# Keypad.net
KiCad netlist of a schematic drawn in EAGLE
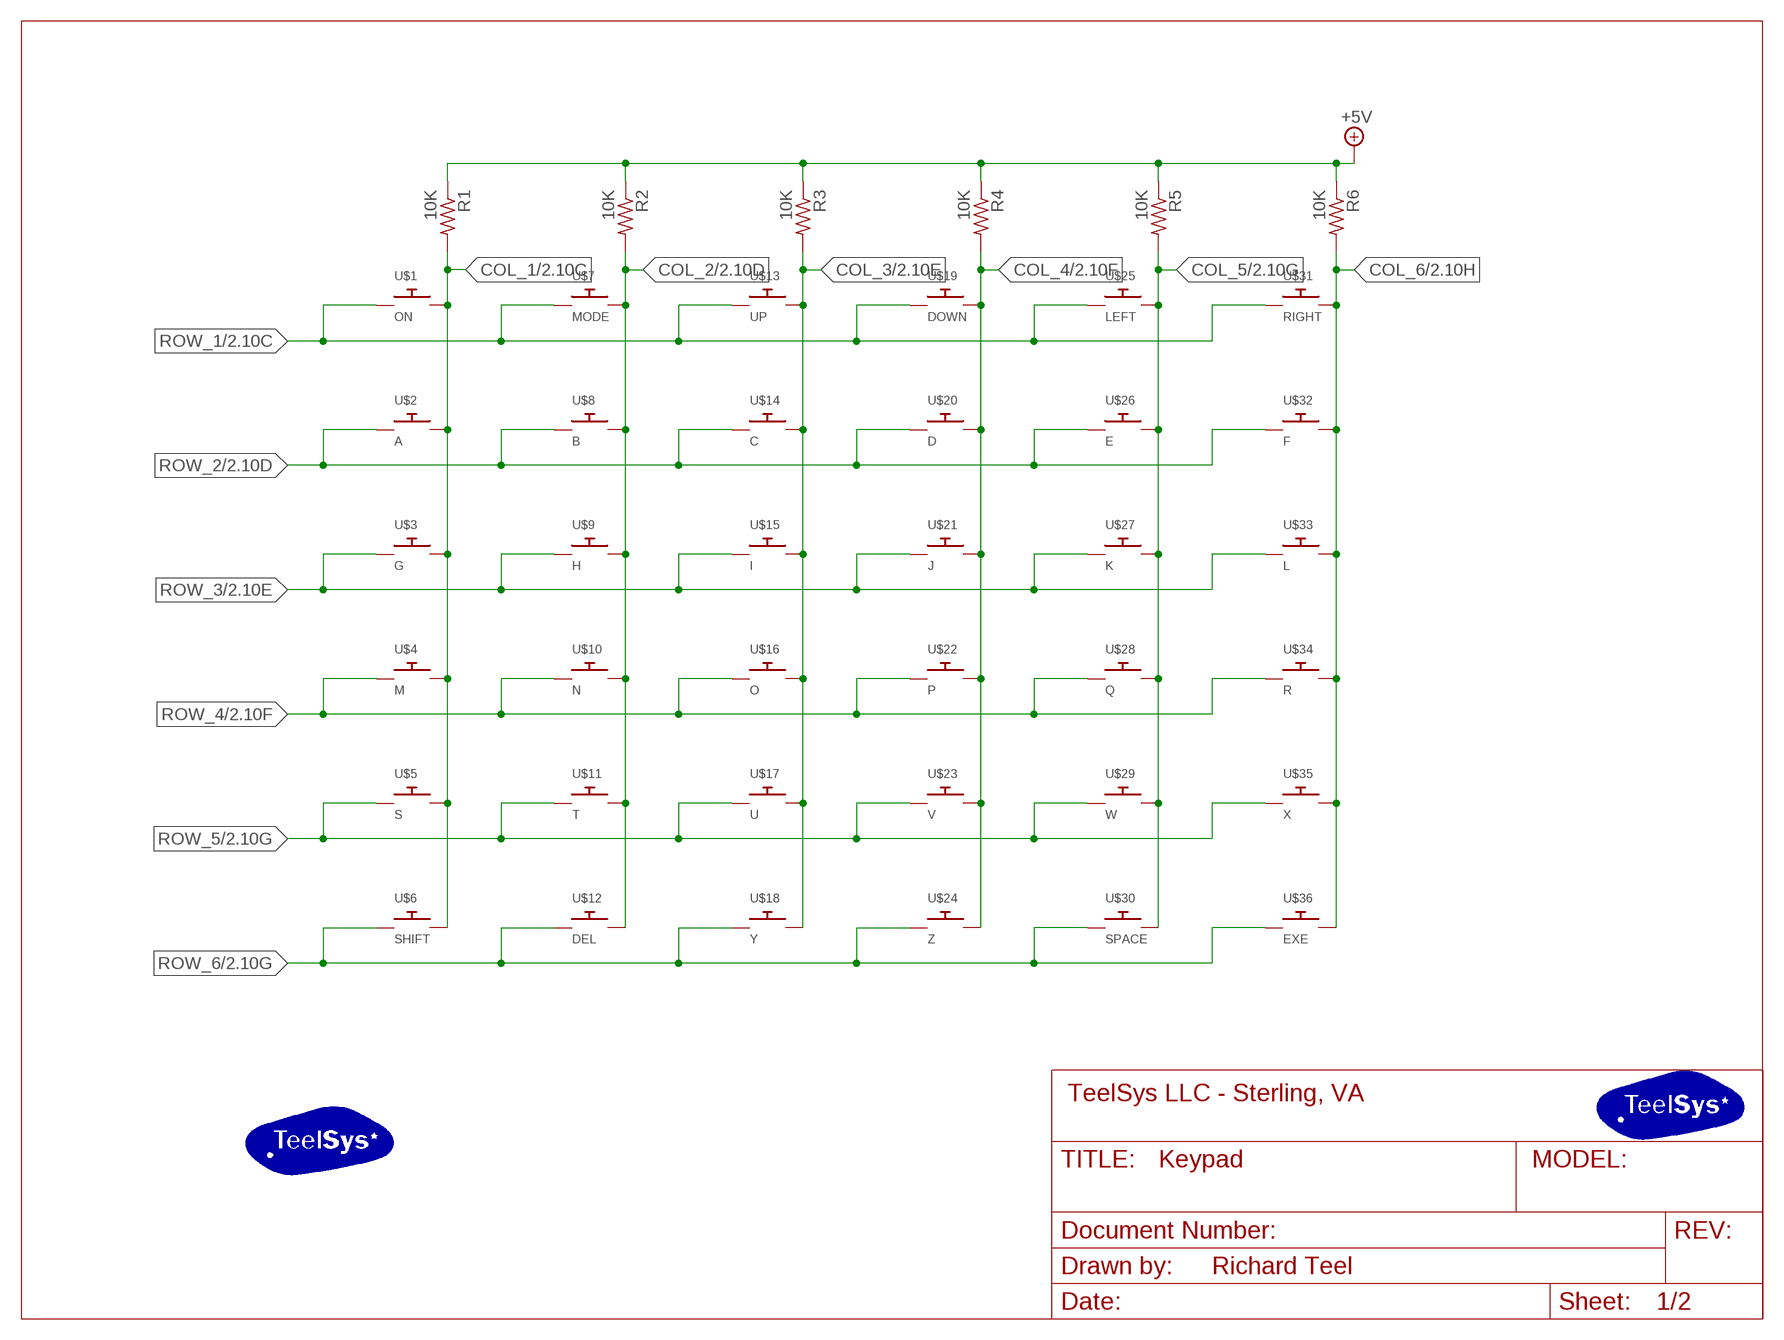
[diagram p0: schematic, sheet 1]
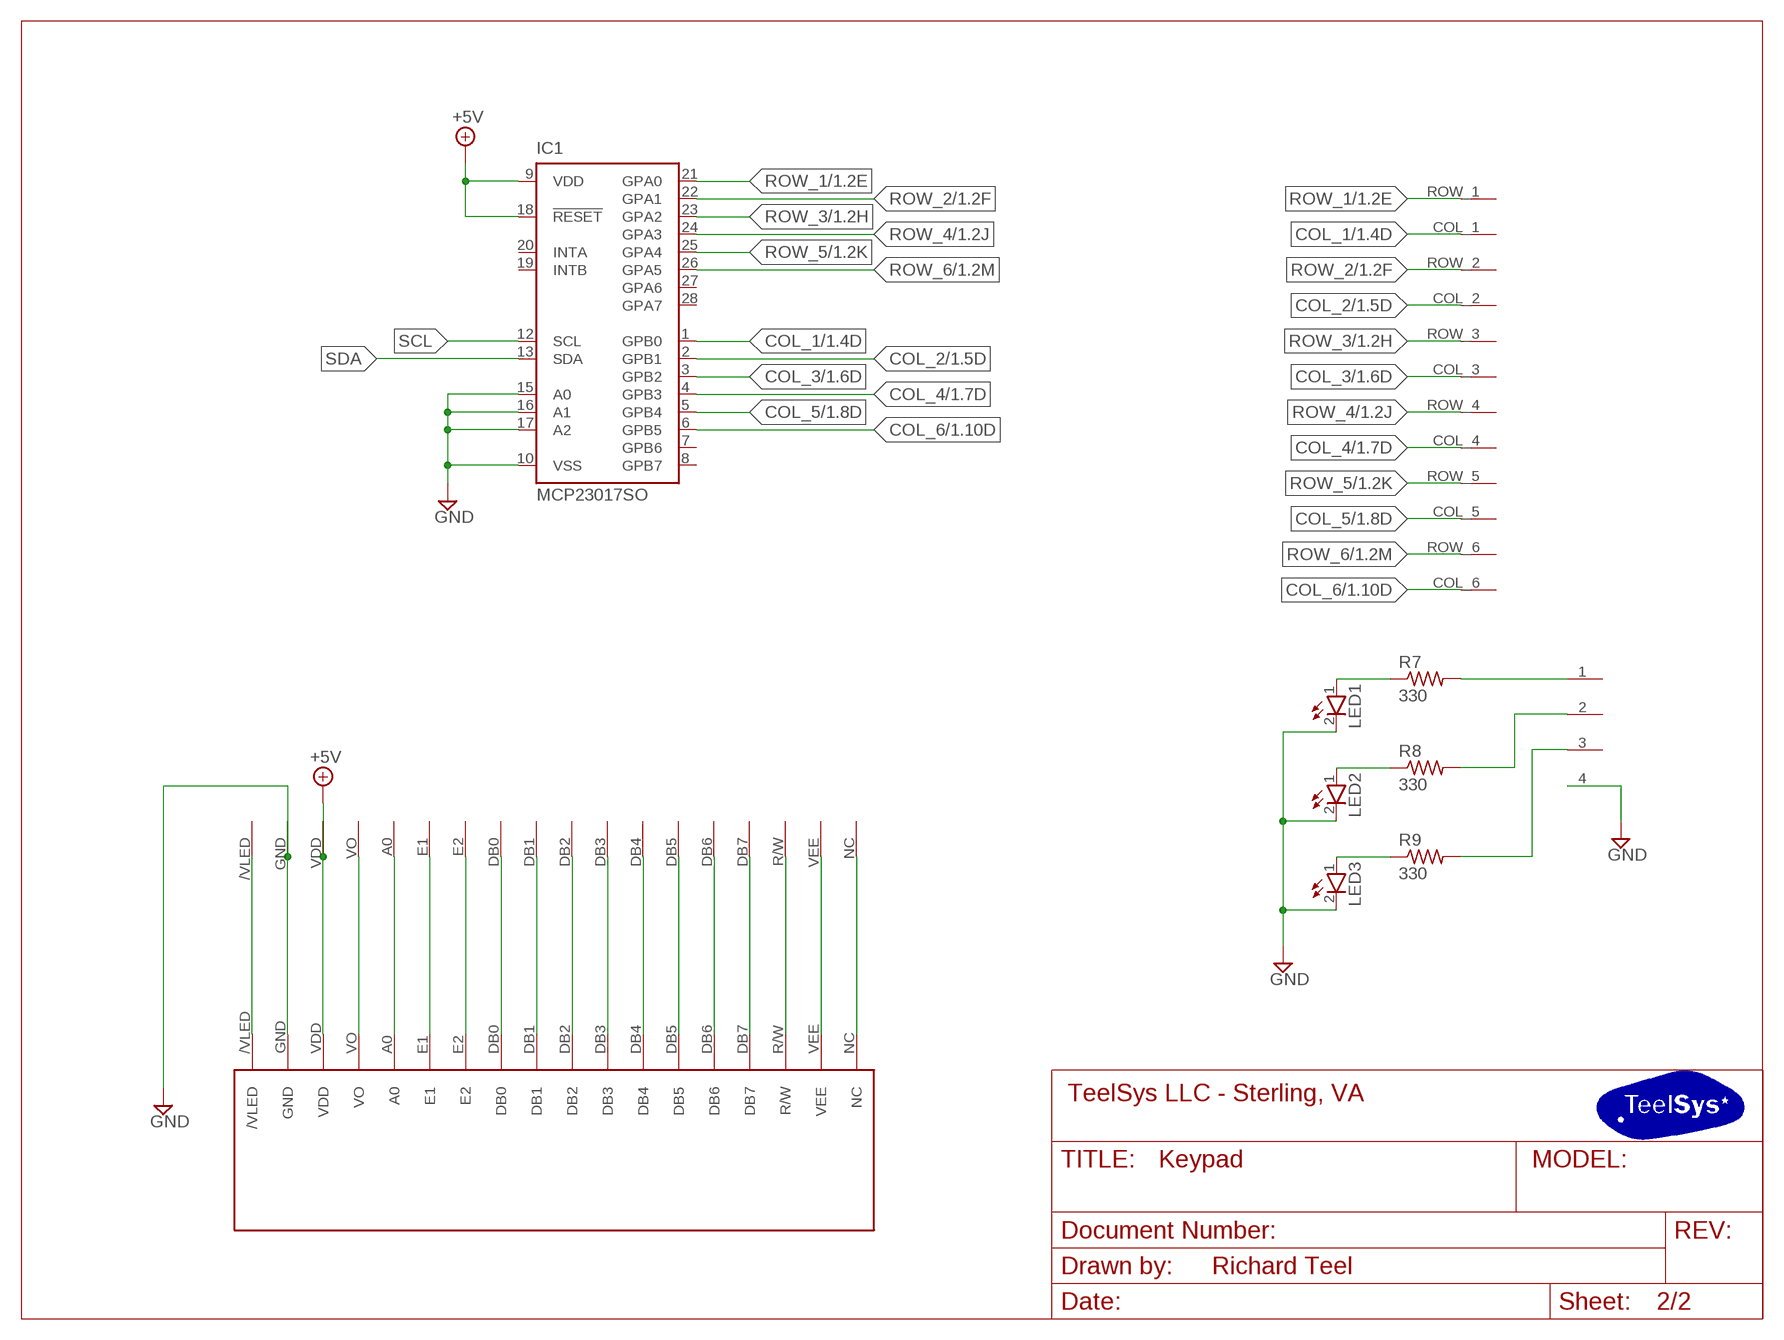
[diagram p1: schematic, sheet 2]

(export (version "E")
  (design (tool "Eeschema 10.0.6"))
  (components
    (comp (ref "R1")
      (value "10K")
      (footprint "eagle-import:M0805")
      (libsource (lib "eagle-import") (part "R-US_M0805"))
    )
    (comp (ref "R2")
      (value "10K")
      (footprint "eagle-import:M0805")
      (libsource (lib "eagle-import") (part "R-US_M0805"))
    )
    (comp (ref "R3")
      (value "10K")
      (footprint "eagle-import:M0805")
      (libsource (lib "eagle-import") (part "R-US_M0805"))
    )
    (comp (ref "R4")
      (value "10K")
      (footprint "eagle-import:M0805")
      (libsource (lib "eagle-import") (part "R-US_M0805"))
    )
    (comp (ref "R5")
      (value "10K")
      (footprint "eagle-import:M0805")
      (libsource (lib "eagle-import") (part "R-US_M0805"))
    )
    (comp (ref "R6")
      (value "10K")
      (footprint "eagle-import:M0805")
      (libsource (lib "eagle-import") (part "R-US_M0805"))
    )
    (comp (ref "U$1")
      (value "ON")
      (footprint "eagle-import:KEYPAD_RND")
      (libsource (lib "eagle-import") (part "KEYPAD"))
    )
    (comp (ref "U$2")
      (value "A")
      (footprint "eagle-import:KEYPAD_RND")
      (libsource (lib "eagle-import") (part "KEYPAD"))
    )
    (comp (ref "U$3")
      (value "G")
      (footprint "eagle-import:KEYPAD_RND")
      (libsource (lib "eagle-import") (part "KEYPAD"))
    )
    (comp (ref "U$4")
      (value "M")
      (footprint "eagle-import:KEYPAD_RND")
      (libsource (lib "eagle-import") (part "KEYPAD"))
    )
    (comp (ref "U$5")
      (value "S")
      (footprint "eagle-import:KEYPAD_RND")
      (libsource (lib "eagle-import") (part "KEYPAD"))
    )
    (comp (ref "U$6")
      (value "SHIFT")
      (footprint "eagle-import:KEYPAD_RND")
      (libsource (lib "eagle-import") (part "KEYPAD"))
    )
    (comp (ref "U$7")
      (value "MODE")
      (footprint "eagle-import:KEYPAD_RND")
      (libsource (lib "eagle-import") (part "KEYPAD"))
    )
    (comp (ref "U$8")
      (value "B")
      (footprint "eagle-import:KEYPAD_RND")
      (libsource (lib "eagle-import") (part "KEYPAD"))
    )
    (comp (ref "U$9")
      (value "H")
      (footprint "eagle-import:KEYPAD_RND")
      (libsource (lib "eagle-import") (part "KEYPAD"))
    )
    (comp (ref "U$10")
      (value "N")
      (footprint "eagle-import:KEYPAD_RND")
      (libsource (lib "eagle-import") (part "KEYPAD"))
    )
    (comp (ref "U$11")
      (value "T")
      (footprint "eagle-import:KEYPAD_RND")
      (libsource (lib "eagle-import") (part "KEYPAD"))
    )
    (comp (ref "U$12")
      (value "DEL")
      (footprint "eagle-import:KEYPAD_RND")
      (libsource (lib "eagle-import") (part "KEYPAD"))
    )
    (comp (ref "U$13")
      (value "UP")
      (footprint "eagle-import:KEYPAD_RND")
      (libsource (lib "eagle-import") (part "KEYPAD"))
    )
    (comp (ref "U$14")
      (value "C")
      (footprint "eagle-import:KEYPAD_RND")
      (libsource (lib "eagle-import") (part "KEYPAD"))
    )
    (comp (ref "U$15")
      (value "I")
      (footprint "eagle-import:KEYPAD_RND")
      (libsource (lib "eagle-import") (part "KEYPAD"))
    )
    (comp (ref "U$16")
      (value "O")
      (footprint "eagle-import:KEYPAD_RND")
      (libsource (lib "eagle-import") (part "KEYPAD"))
    )
    (comp (ref "U$17")
      (value "U")
      (footprint "eagle-import:KEYPAD_RND")
      (libsource (lib "eagle-import") (part "KEYPAD"))
    )
    (comp (ref "U$18")
      (value "Y")
      (footprint "eagle-import:KEYPAD_RND")
      (libsource (lib "eagle-import") (part "KEYPAD"))
    )
    (comp (ref "U$19")
      (value "DOWN")
      (footprint "eagle-import:KEYPAD_RND")
      (libsource (lib "eagle-import") (part "KEYPAD"))
    )
    (comp (ref "U$20")
      (value "D")
      (footprint "eagle-import:KEYPAD_RND")
      (libsource (lib "eagle-import") (part "KEYPAD"))
    )
    (comp (ref "U$21")
      (value "J")
      (footprint "eagle-import:KEYPAD_RND")
      (libsource (lib "eagle-import") (part "KEYPAD"))
    )
    (comp (ref "U$22")
      (value "P")
      (footprint "eagle-import:KEYPAD_RND")
      (libsource (lib "eagle-import") (part "KEYPAD"))
    )
    (comp (ref "U$23")
      (value "V")
      (footprint "eagle-import:KEYPAD_RND")
      (libsource (lib "eagle-import") (part "KEYPAD"))
    )
    (comp (ref "U$24")
      (value "Z")
      (footprint "eagle-import:KEYPAD_RND")
      (libsource (lib "eagle-import") (part "KEYPAD"))
    )
    (comp (ref "U$25")
      (value "LEFT")
      (footprint "eagle-import:KEYPAD_RND")
      (libsource (lib "eagle-import") (part "KEYPAD"))
    )
    (comp (ref "U$26")
      (value "E")
      (footprint "eagle-import:KEYPAD_RND")
      (libsource (lib "eagle-import") (part "KEYPAD"))
    )
    (comp (ref "U$27")
      (value "K")
      (footprint "eagle-import:KEYPAD_RND")
      (libsource (lib "eagle-import") (part "KEYPAD"))
    )
    (comp (ref "U$28")
      (value "Q")
      (footprint "eagle-import:KEYPAD_RND")
      (libsource (lib "eagle-import") (part "KEYPAD"))
    )
    (comp (ref "U$29")
      (value "W")
      (footprint "eagle-import:KEYPAD_RND")
      (libsource (lib "eagle-import") (part "KEYPAD"))
    )
    (comp (ref "U$30")
      (value "SPACE")
      (footprint "eagle-import:KEYPAD_RND")
      (libsource (lib "eagle-import") (part "KEYPAD"))
    )
    (comp (ref "U$31")
      (value "RIGHT")
      (footprint "eagle-import:KEYPAD_RND")
      (libsource (lib "eagle-import") (part "KEYPAD"))
    )
    (comp (ref "U$32")
      (value "F")
      (footprint "eagle-import:KEYPAD_RND")
      (libsource (lib "eagle-import") (part "KEYPAD"))
    )
    (comp (ref "U$33")
      (value "L")
      (footprint "eagle-import:KEYPAD_RND")
      (libsource (lib "eagle-import") (part "KEYPAD"))
    )
    (comp (ref "U$34")
      (value "R")
      (footprint "eagle-import:KEYPAD_RND")
      (libsource (lib "eagle-import") (part "KEYPAD"))
    )
    (comp (ref "U$35")
      (value "X")
      (footprint "eagle-import:KEYPAD_RND")
      (libsource (lib "eagle-import") (part "KEYPAD"))
    )
    (comp (ref "U$36")
      (value "EXE")
      (footprint "eagle-import:KEYPAD_RND")
      (libsource (lib "eagle-import") (part "KEYPAD"))
    )
    (comp (ref "U$40")
      (value "TEELSYS_LOGO_ART_2BOTTOM")
      (footprint "eagle-import:TEELSYS_LOGO_ART_BOTTOM_2")
      (libsource (lib "eagle-import") (part "TEELSYS_LOGO_ART_2BOTTOM"))
    )
    (comp (ref "IC1")
      (value "MCP23017SO")
      (footprint "eagle-import:SO28W")
      (fields (field (name "MF") "MICROCHIP") (field (name "MPN") "MCP23017-E/SO"))
      (libsource (lib "eagle-import") (part "MCP23017SO"))
    )
    (comp (ref "LED1")
      (value "RED")
      (footprint "eagle-import:HEADER-1X2")
      (libsource (lib "eagle-import") (part "LED"))
    )
    (comp (ref "LED2")
      (value "Green")
      (footprint "eagle-import:HEADER-1X2")
      (libsource (lib "eagle-import") (part "LED"))
    )
    (comp (ref "LED3")
      (value "BLUE")
      (footprint "eagle-import:HEADER-1X2")
      (libsource (lib "eagle-import") (part "LED"))
    )
    (comp (ref "R7")
      (value "330")
      (footprint "eagle-import:M0805")
      (libsource (lib "eagle-import") (part "R-US_M0805"))
    )
    (comp (ref "R8")
      (value "330")
      (footprint "eagle-import:M0805")
      (libsource (lib "eagle-import") (part "R-US_M0805"))
    )
    (comp (ref "R9")
      (value "330")
      (footprint "eagle-import:M0805")
      (libsource (lib "eagle-import") (part "R-US_M0805"))
    )
    (comp (ref "U$37")
      (value "HEADER-1X12-KEYPAD")
      (footprint "eagle-import:HEADER-1X12-KEYPAD")
      (libsource (lib "eagle-import") (part "HEADER-1X12-KEYPAD"))
    )
    (comp (ref "U$38")
      (value "HEADER-1X18-LCD")
      (footprint "eagle-import:HEADER-1X18-LCD")
      (libsource (lib "eagle-import") (part "HEADER-1X18-LCD"))
    )
    (comp (ref "U$39")
      (value "HEADER-1X4")
      (footprint "eagle-import:HEADER-1X4")
      (libsource (lib "eagle-import") (part "HEADER-1X4"))
    )
    (comp (ref "U$73")
      (value "LCD_CFAL12832A022")
      (footprint "eagle-import:LCD_CFAL12832A022")
      (libsource (lib "eagle-import") (part "LCD_CFAL12832A022"))
    )
  )
  (nets
    (net (code "1") (name "+5V") (class "Default")
      (node (ref "IC1") (pin "18") (pinfunction "~{RESET}_18") (pintype "input"))
      (node (ref "IC1") (pin "9") (pinfunction "VDD_9") (pintype "power_in"))
      (node (ref "R1") (pin "1") (pinfunction "1_1") (pintype "passive"))
      (node (ref "R2") (pin "1") (pinfunction "1_1") (pintype "passive"))
      (node (ref "R3") (pin "1") (pinfunction "1_1") (pintype "passive"))
      (node (ref "R4") (pin "1") (pinfunction "1_1") (pintype "passive"))
      (node (ref "R5") (pin "1") (pinfunction "1_1") (pintype "passive"))
      (node (ref "R6") (pin "1") (pinfunction "1_1") (pintype "passive"))
      (node (ref "U$38") (pin "VDD") (pinfunction "VDD_VDD") (pintype "bidirectional"))
      (node (ref "U$73") (pin "VDD") (pinfunction "VDD_VDD") (pintype "bidirectional"))
    )
    (net (code "2") (name "COL_1") (class "Default")
      (node (ref "IC1") (pin "1") (pinfunction "GPB0_1") (pintype "bidirectional"))
      (node (ref "R1") (pin "2") (pinfunction "2_2") (pintype "passive"))
      (node (ref "U$1") (pin "P$2") (pinfunction "P$2_P$2") (pintype "passive"))
      (node (ref "U$2") (pin "P$2") (pinfunction "P$2_P$2") (pintype "passive"))
      (node (ref "U$3") (pin "P$2") (pinfunction "P$2_P$2") (pintype "passive"))
      (node (ref "U$37") (pin "COL_1") (pinfunction "COL_1_COL_1") (pintype "bidirectional"))
      (node (ref "U$4") (pin "P$2") (pinfunction "P$2_P$2") (pintype "passive"))
      (node (ref "U$5") (pin "P$2") (pinfunction "P$2_P$2") (pintype "passive"))
      (node (ref "U$6") (pin "P$2") (pinfunction "P$2_P$2") (pintype "passive"))
    )
    (net (code "3") (name "COL_2") (class "Default")
      (node (ref "IC1") (pin "2") (pinfunction "GPB1_2") (pintype "bidirectional"))
      (node (ref "R2") (pin "2") (pinfunction "2_2") (pintype "passive"))
      (node (ref "U$10") (pin "P$2") (pinfunction "P$2_P$2") (pintype "passive"))
      (node (ref "U$11") (pin "P$2") (pinfunction "P$2_P$2") (pintype "passive"))
      (node (ref "U$12") (pin "P$2") (pinfunction "P$2_P$2") (pintype "passive"))
      (node (ref "U$37") (pin "COL_2") (pinfunction "COL_2_COL_2") (pintype "bidirectional"))
      (node (ref "U$7") (pin "P$2") (pinfunction "P$2_P$2") (pintype "passive"))
      (node (ref "U$8") (pin "P$2") (pinfunction "P$2_P$2") (pintype "passive"))
      (node (ref "U$9") (pin "P$2") (pinfunction "P$2_P$2") (pintype "passive"))
    )
    (net (code "4") (name "COL_3") (class "Default")
      (node (ref "IC1") (pin "3") (pinfunction "GPB2_3") (pintype "bidirectional"))
      (node (ref "R3") (pin "2") (pinfunction "2_2") (pintype "passive"))
      (node (ref "U$13") (pin "P$2") (pinfunction "P$2_P$2") (pintype "passive"))
      (node (ref "U$14") (pin "P$2") (pinfunction "P$2_P$2") (pintype "passive"))
      (node (ref "U$15") (pin "P$2") (pinfunction "P$2_P$2") (pintype "passive"))
      (node (ref "U$16") (pin "P$2") (pinfunction "P$2_P$2") (pintype "passive"))
      (node (ref "U$17") (pin "P$2") (pinfunction "P$2_P$2") (pintype "passive"))
      (node (ref "U$18") (pin "P$2") (pinfunction "P$2_P$2") (pintype "passive"))
      (node (ref "U$37") (pin "COL_3") (pinfunction "COL_3_COL_3") (pintype "bidirectional"))
    )
    (net (code "5") (name "COL_4") (class "Default")
      (node (ref "IC1") (pin "4") (pinfunction "GPB3_4") (pintype "bidirectional"))
      (node (ref "R4") (pin "2") (pinfunction "2_2") (pintype "passive"))
      (node (ref "U$19") (pin "P$2") (pinfunction "P$2_P$2") (pintype "passive"))
      (node (ref "U$20") (pin "P$2") (pinfunction "P$2_P$2") (pintype "passive"))
      (node (ref "U$21") (pin "P$2") (pinfunction "P$2_P$2") (pintype "passive"))
      (node (ref "U$22") (pin "P$2") (pinfunction "P$2_P$2") (pintype "passive"))
      (node (ref "U$23") (pin "P$2") (pinfunction "P$2_P$2") (pintype "passive"))
      (node (ref "U$24") (pin "P$2") (pinfunction "P$2_P$2") (pintype "passive"))
      (node (ref "U$37") (pin "COL_4") (pinfunction "COL_4_COL_4") (pintype "bidirectional"))
    )
    (net (code "6") (name "COL_5") (class "Default")
      (node (ref "IC1") (pin "5") (pinfunction "GPB4_5") (pintype "bidirectional"))
      (node (ref "R5") (pin "2") (pinfunction "2_2") (pintype "passive"))
      (node (ref "U$25") (pin "P$2") (pinfunction "P$2_P$2") (pintype "passive"))
      (node (ref "U$26") (pin "P$2") (pinfunction "P$2_P$2") (pintype "passive"))
      (node (ref "U$27") (pin "P$2") (pinfunction "P$2_P$2") (pintype "passive"))
      (node (ref "U$28") (pin "P$2") (pinfunction "P$2_P$2") (pintype "passive"))
      (node (ref "U$29") (pin "P$2") (pinfunction "P$2_P$2") (pintype "passive"))
      (node (ref "U$30") (pin "P$2") (pinfunction "P$2_P$2") (pintype "passive"))
      (node (ref "U$37") (pin "COL_5") (pinfunction "COL_5_COL_5") (pintype "bidirectional"))
    )
    (net (code "7") (name "COL_6") (class "Default")
      (node (ref "IC1") (pin "6") (pinfunction "GPB5_6") (pintype "bidirectional"))
      (node (ref "R6") (pin "2") (pinfunction "2_2") (pintype "passive"))
      (node (ref "U$31") (pin "P$2") (pinfunction "P$2_P$2") (pintype "passive"))
      (node (ref "U$32") (pin "P$2") (pinfunction "P$2_P$2") (pintype "passive"))
      (node (ref "U$33") (pin "P$2") (pinfunction "P$2_P$2") (pintype "passive"))
      (node (ref "U$34") (pin "P$2") (pinfunction "P$2_P$2") (pintype "passive"))
      (node (ref "U$35") (pin "P$2") (pinfunction "P$2_P$2") (pintype "passive"))
      (node (ref "U$36") (pin "P$2") (pinfunction "P$2_P$2") (pintype "passive"))
      (node (ref "U$37") (pin "COL_6") (pinfunction "COL_6_COL_6") (pintype "bidirectional"))
    )
    (net (code "8") (name "GND") (class "Default")
      (node (ref "IC1") (pin "10") (pinfunction "VSS_10") (pintype "power_in"))
      (node (ref "IC1") (pin "15") (pinfunction "A0_15") (pintype "input"))
      (node (ref "IC1") (pin "16") (pinfunction "A1_16") (pintype "input"))
      (node (ref "IC1") (pin "17") (pinfunction "A2_17") (pintype "input"))
      (node (ref "LED1") (pin "2") (pinfunction "K_2") (pintype "bidirectional"))
      (node (ref "LED2") (pin "2") (pinfunction "K_2") (pintype "bidirectional"))
      (node (ref "LED3") (pin "2") (pinfunction "K_2") (pintype "bidirectional"))
      (node (ref "U$38") (pin "GND") (pinfunction "GND_GND") (pintype "bidirectional"))
      (node (ref "U$39") (pin "4") (pinfunction "4_4") (pintype "bidirectional"))
      (node (ref "U$73") (pin "GND") (pinfunction "GND_GND") (pintype "bidirectional"))
    )
    (net (code "9") (name "Net-(LED1-A)") (class "Default")
      (node (ref "LED1") (pin "1") (pinfunction "A_1") (pintype "bidirectional"))
      (node (ref "R7") (pin "1") (pinfunction "1_1") (pintype "passive"))
    )
    (net (code "10") (name "Net-(LED2-A)") (class "Default")
      (node (ref "LED2") (pin "1") (pinfunction "A_1") (pintype "bidirectional"))
      (node (ref "R8") (pin "1") (pinfunction "1_1") (pintype "passive"))
    )
    (net (code "11") (name "Net-(LED3-A)") (class "Default")
      (node (ref "LED3") (pin "1") (pinfunction "A_1") (pintype "bidirectional"))
      (node (ref "R9") (pin "1") (pinfunction "1_1") (pintype "passive"))
    )
    (net (code "12") (name "Net-(R7-Pad2)") (class "Default")
      (node (ref "R7") (pin "2") (pinfunction "2_2") (pintype "passive"))
      (node (ref "U$39") (pin "1") (pinfunction "1_1") (pintype "bidirectional"))
    )
    (net (code "13") (name "Net-(R8-Pad2)") (class "Default")
      (node (ref "R8") (pin "2") (pinfunction "2_2") (pintype "passive"))
      (node (ref "U$39") (pin "2") (pinfunction "2_2") (pintype "bidirectional"))
    )
    (net (code "14") (name "Net-(R9-Pad2)") (class "Default")
      (node (ref "R9") (pin "2") (pinfunction "2_2") (pintype "passive"))
      (node (ref "U$39") (pin "3") (pinfunction "3_3") (pintype "bidirectional"))
    )
    (net (code "15") (name "Net-(U$38-PadA0)") (class "Default")
      (node (ref "U$38") (pin "A0") (pinfunction "A0_A0") (pintype "bidirectional"))
      (node (ref "U$73") (pin "A0") (pinfunction "A0_A0") (pintype "bidirectional"))
    )
    (net (code "16") (name "Net-(U$38-PadDB0)") (class "Default")
      (node (ref "U$38") (pin "DB0") (pinfunction "DB0_DB0") (pintype "bidirectional"))
      (node (ref "U$73") (pin "DB0") (pinfunction "DB0_DB0") (pintype "bidirectional"))
    )
    (net (code "17") (name "Net-(U$38-PadDB1)") (class "Default")
      (node (ref "U$38") (pin "DB1") (pinfunction "DB1_DB1") (pintype "bidirectional"))
      (node (ref "U$73") (pin "DB1") (pinfunction "DB1_DB1") (pintype "bidirectional"))
    )
    (net (code "18") (name "Net-(U$38-PadDB2)") (class "Default")
      (node (ref "U$38") (pin "DB2") (pinfunction "DB2_DB2") (pintype "bidirectional"))
      (node (ref "U$73") (pin "DB2") (pinfunction "DB2_DB2") (pintype "bidirectional"))
    )
    (net (code "19") (name "Net-(U$38-PadDB3)") (class "Default")
      (node (ref "U$38") (pin "DB3") (pinfunction "DB3_DB3") (pintype "bidirectional"))
      (node (ref "U$73") (pin "DB3") (pinfunction "DB3_DB3") (pintype "bidirectional"))
    )
    (net (code "20") (name "Net-(U$38-PadDB4)") (class "Default")
      (node (ref "U$38") (pin "DB4") (pinfunction "DB4_DB4") (pintype "bidirectional"))
      (node (ref "U$73") (pin "DB4") (pinfunction "DB4_DB4") (pintype "bidirectional"))
    )
    (net (code "21") (name "Net-(U$38-PadDB5)") (class "Default")
      (node (ref "U$38") (pin "DB5") (pinfunction "DB5_DB5") (pintype "bidirectional"))
      (node (ref "U$73") (pin "DB5") (pinfunction "DB5_DB5") (pintype "bidirectional"))
    )
    (net (code "22") (name "Net-(U$38-PadDB6)") (class "Default")
      (node (ref "U$38") (pin "DB6") (pinfunction "DB6_DB6") (pintype "bidirectional"))
      (node (ref "U$73") (pin "DB6") (pinfunction "DB6_DB6") (pintype "bidirectional"))
    )
    (net (code "23") (name "Net-(U$38-PadDB7)") (class "Default")
      (node (ref "U$38") (pin "DB7") (pinfunction "DB7_DB7") (pintype "bidirectional"))
      (node (ref "U$73") (pin "DB7") (pinfunction "DB7_DB7") (pintype "bidirectional"))
    )
    (net (code "24") (name "Net-(U$38-PadE1)") (class "Default")
      (node (ref "U$38") (pin "E1") (pinfunction "E1_E1") (pintype "bidirectional"))
      (node (ref "U$73") (pin "E1") (pinfunction "E1_E1") (pintype "bidirectional"))
    )
    (net (code "25") (name "Net-(U$38-PadE2)") (class "Default")
      (node (ref "U$38") (pin "E2") (pinfunction "E2_E2") (pintype "bidirectional"))
      (node (ref "U$73") (pin "E2") (pinfunction "E2_E2") (pintype "bidirectional"))
    )
    (net (code "26") (name "Net-(U$38-PadNC)") (class "Default")
      (node (ref "U$38") (pin "NC") (pinfunction "NC_NC") (pintype "bidirectional"))
      (node (ref "U$73") (pin "NC") (pinfunction "NC_NC") (pintype "bidirectional"))
    )
    (net (code "27") (name "Net-(U$38-PadR{slash}W)") (class "Default")
      (node (ref "U$38") (pin "R/W") (pinfunction "R/W_R/W") (pintype "bidirectional"))
      (node (ref "U$73") (pin "R/W") (pinfunction "R/W_R/W") (pintype "bidirectional"))
    )
    (net (code "28") (name "Net-(U$38-PadVEE)") (class "Default")
      (node (ref "U$38") (pin "VEE") (pinfunction "VEE_VEE") (pintype "bidirectional"))
      (node (ref "U$73") (pin "VEE") (pinfunction "VEE_VEE") (pintype "bidirectional"))
    )
    (net (code "29") (name "Net-(U$38-PadVO)") (class "Default")
      (node (ref "U$38") (pin "VO") (pinfunction "VO_VO") (pintype "bidirectional"))
      (node (ref "U$73") (pin "VO") (pinfunction "VO_VO") (pintype "bidirectional"))
    )
    (net (code "30") (name "Net-(U$38-Pad{slash}VLED)") (class "Default")
      (node (ref "U$38") (pin "/VLED") (pinfunction "/VLED_/VLED") (pintype "bidirectional"))
      (node (ref "U$73") (pin "/VLED") (pinfunction "/VLED_/VLED") (pintype "bidirectional"))
    )
    (net (code "31") (name "ROW_1") (class "Default")
      (node (ref "IC1") (pin "21") (pinfunction "GPA0_21") (pintype "bidirectional"))
      (node (ref "U$1") (pin "P$1") (pinfunction "P$1_P$1") (pintype "passive"))
      (node (ref "U$13") (pin "P$1") (pinfunction "P$1_P$1") (pintype "passive"))
      (node (ref "U$19") (pin "P$1") (pinfunction "P$1_P$1") (pintype "passive"))
      (node (ref "U$25") (pin "P$1") (pinfunction "P$1_P$1") (pintype "passive"))
      (node (ref "U$31") (pin "P$1") (pinfunction "P$1_P$1") (pintype "passive"))
      (node (ref "U$37") (pin "ROW_1") (pinfunction "ROW_1_ROW_1") (pintype "bidirectional"))
      (node (ref "U$7") (pin "P$1") (pinfunction "P$1_P$1") (pintype "passive"))
    )
    (net (code "32") (name "ROW_2") (class "Default")
      (node (ref "IC1") (pin "22") (pinfunction "GPA1_22") (pintype "bidirectional"))
      (node (ref "U$14") (pin "P$1") (pinfunction "P$1_P$1") (pintype "passive"))
      (node (ref "U$2") (pin "P$1") (pinfunction "P$1_P$1") (pintype "passive"))
      (node (ref "U$20") (pin "P$1") (pinfunction "P$1_P$1") (pintype "passive"))
      (node (ref "U$26") (pin "P$1") (pinfunction "P$1_P$1") (pintype "passive"))
      (node (ref "U$32") (pin "P$1") (pinfunction "P$1_P$1") (pintype "passive"))
      (node (ref "U$37") (pin "ROW_2") (pinfunction "ROW_2_ROW_2") (pintype "bidirectional"))
      (node (ref "U$8") (pin "P$1") (pinfunction "P$1_P$1") (pintype "passive"))
    )
    (net (code "33") (name "ROW_3") (class "Default")
      (node (ref "IC1") (pin "23") (pinfunction "GPA2_23") (pintype "bidirectional"))
      (node (ref "U$15") (pin "P$1") (pinfunction "P$1_P$1") (pintype "passive"))
      (node (ref "U$21") (pin "P$1") (pinfunction "P$1_P$1") (pintype "passive"))
      (node (ref "U$27") (pin "P$1") (pinfunction "P$1_P$1") (pintype "passive"))
      (node (ref "U$3") (pin "P$1") (pinfunction "P$1_P$1") (pintype "passive"))
      (node (ref "U$33") (pin "P$1") (pinfunction "P$1_P$1") (pintype "passive"))
      (node (ref "U$37") (pin "ROW_3") (pinfunction "ROW_3_ROW_3") (pintype "bidirectional"))
      (node (ref "U$9") (pin "P$1") (pinfunction "P$1_P$1") (pintype "passive"))
    )
    (net (code "34") (name "ROW_4") (class "Default")
      (node (ref "IC1") (pin "24") (pinfunction "GPA3_24") (pintype "bidirectional"))
      (node (ref "U$10") (pin "P$1") (pinfunction "P$1_P$1") (pintype "passive"))
      (node (ref "U$16") (pin "P$1") (pinfunction "P$1_P$1") (pintype "passive"))
      (node (ref "U$22") (pin "P$1") (pinfunction "P$1_P$1") (pintype "passive"))
      (node (ref "U$28") (pin "P$1") (pinfunction "P$1_P$1") (pintype "passive"))
      (node (ref "U$34") (pin "P$1") (pinfunction "P$1_P$1") (pintype "passive"))
      (node (ref "U$37") (pin "ROW_4") (pinfunction "ROW_4_ROW_4") (pintype "bidirectional"))
      (node (ref "U$4") (pin "P$1") (pinfunction "P$1_P$1") (pintype "passive"))
    )
    (net (code "35") (name "ROW_5") (class "Default")
      (node (ref "IC1") (pin "25") (pinfunction "GPA4_25") (pintype "bidirectional"))
      (node (ref "U$11") (pin "P$1") (pinfunction "P$1_P$1") (pintype "passive"))
      (node (ref "U$17") (pin "P$1") (pinfunction "P$1_P$1") (pintype "passive"))
      (node (ref "U$23") (pin "P$1") (pinfunction "P$1_P$1") (pintype "passive"))
      (node (ref "U$29") (pin "P$1") (pinfunction "P$1_P$1") (pintype "passive"))
      (node (ref "U$35") (pin "P$1") (pinfunction "P$1_P$1") (pintype "passive"))
      (node (ref "U$37") (pin "ROW_5") (pinfunction "ROW_5_ROW_5") (pintype "bidirectional"))
      (node (ref "U$5") (pin "P$1") (pinfunction "P$1_P$1") (pintype "passive"))
    )
    (net (code "36") (name "ROW_6") (class "Default")
      (node (ref "IC1") (pin "26") (pinfunction "GPA5_26") (pintype "bidirectional"))
      (node (ref "U$12") (pin "P$1") (pinfunction "P$1_P$1") (pintype "passive"))
      (node (ref "U$18") (pin "P$1") (pinfunction "P$1_P$1") (pintype "passive"))
      (node (ref "U$24") (pin "P$1") (pinfunction "P$1_P$1") (pintype "passive"))
      (node (ref "U$30") (pin "P$1") (pinfunction "P$1_P$1") (pintype "passive"))
      (node (ref "U$36") (pin "P$1") (pinfunction "P$1_P$1") (pintype "passive"))
      (node (ref "U$37") (pin "ROW_6") (pinfunction "ROW_6_ROW_6") (pintype "bidirectional"))
      (node (ref "U$6") (pin "P$1") (pinfunction "P$1_P$1") (pintype "passive"))
    )
    (net (code "37") (name "SCL") (class "Default")
      (node (ref "IC1") (pin "12") (pinfunction "SCL_12") (pintype "input"))
    )
    (net (code "38") (name "SDA") (class "Default")
      (node (ref "IC1") (pin "13") (pinfunction "SDA_13") (pintype "bidirectional"))
    )
    (net (code "39") (name "unconnected-(IC1-GPA6-Pad27)") (class "Default")
      (node (ref "IC1") (pin "27") (pinfunction "GPA6_27") (pintype "bidirectional"))
    )
    (net (code "40") (name "unconnected-(IC1-GPA7-Pad28)") (class "Default")
      (node (ref "IC1") (pin "28") (pinfunction "GPA7_28") (pintype "bidirectional"))
    )
    (net (code "41") (name "unconnected-(IC1-GPB6-Pad7)") (class "Default")
      (node (ref "IC1") (pin "7") (pinfunction "GPB6_7") (pintype "bidirectional"))
    )
    (net (code "42") (name "unconnected-(IC1-GPB7-Pad8)") (class "Default")
      (node (ref "IC1") (pin "8") (pinfunction "GPB7_8") (pintype "bidirectional"))
    )
    (net (code "43") (name "unconnected-(IC1-INTA-Pad20)") (class "Default")
      (node (ref "IC1") (pin "20") (pinfunction "INTA_20") (pintype "output"))
    )
    (net (code "44") (name "unconnected-(IC1-INTB-Pad19)") (class "Default")
      (node (ref "IC1") (pin "19") (pinfunction "INTB_19") (pintype "output"))
    )
  )
)
